# board.net
KiCad netlist of a schematic drawn in EAGLE
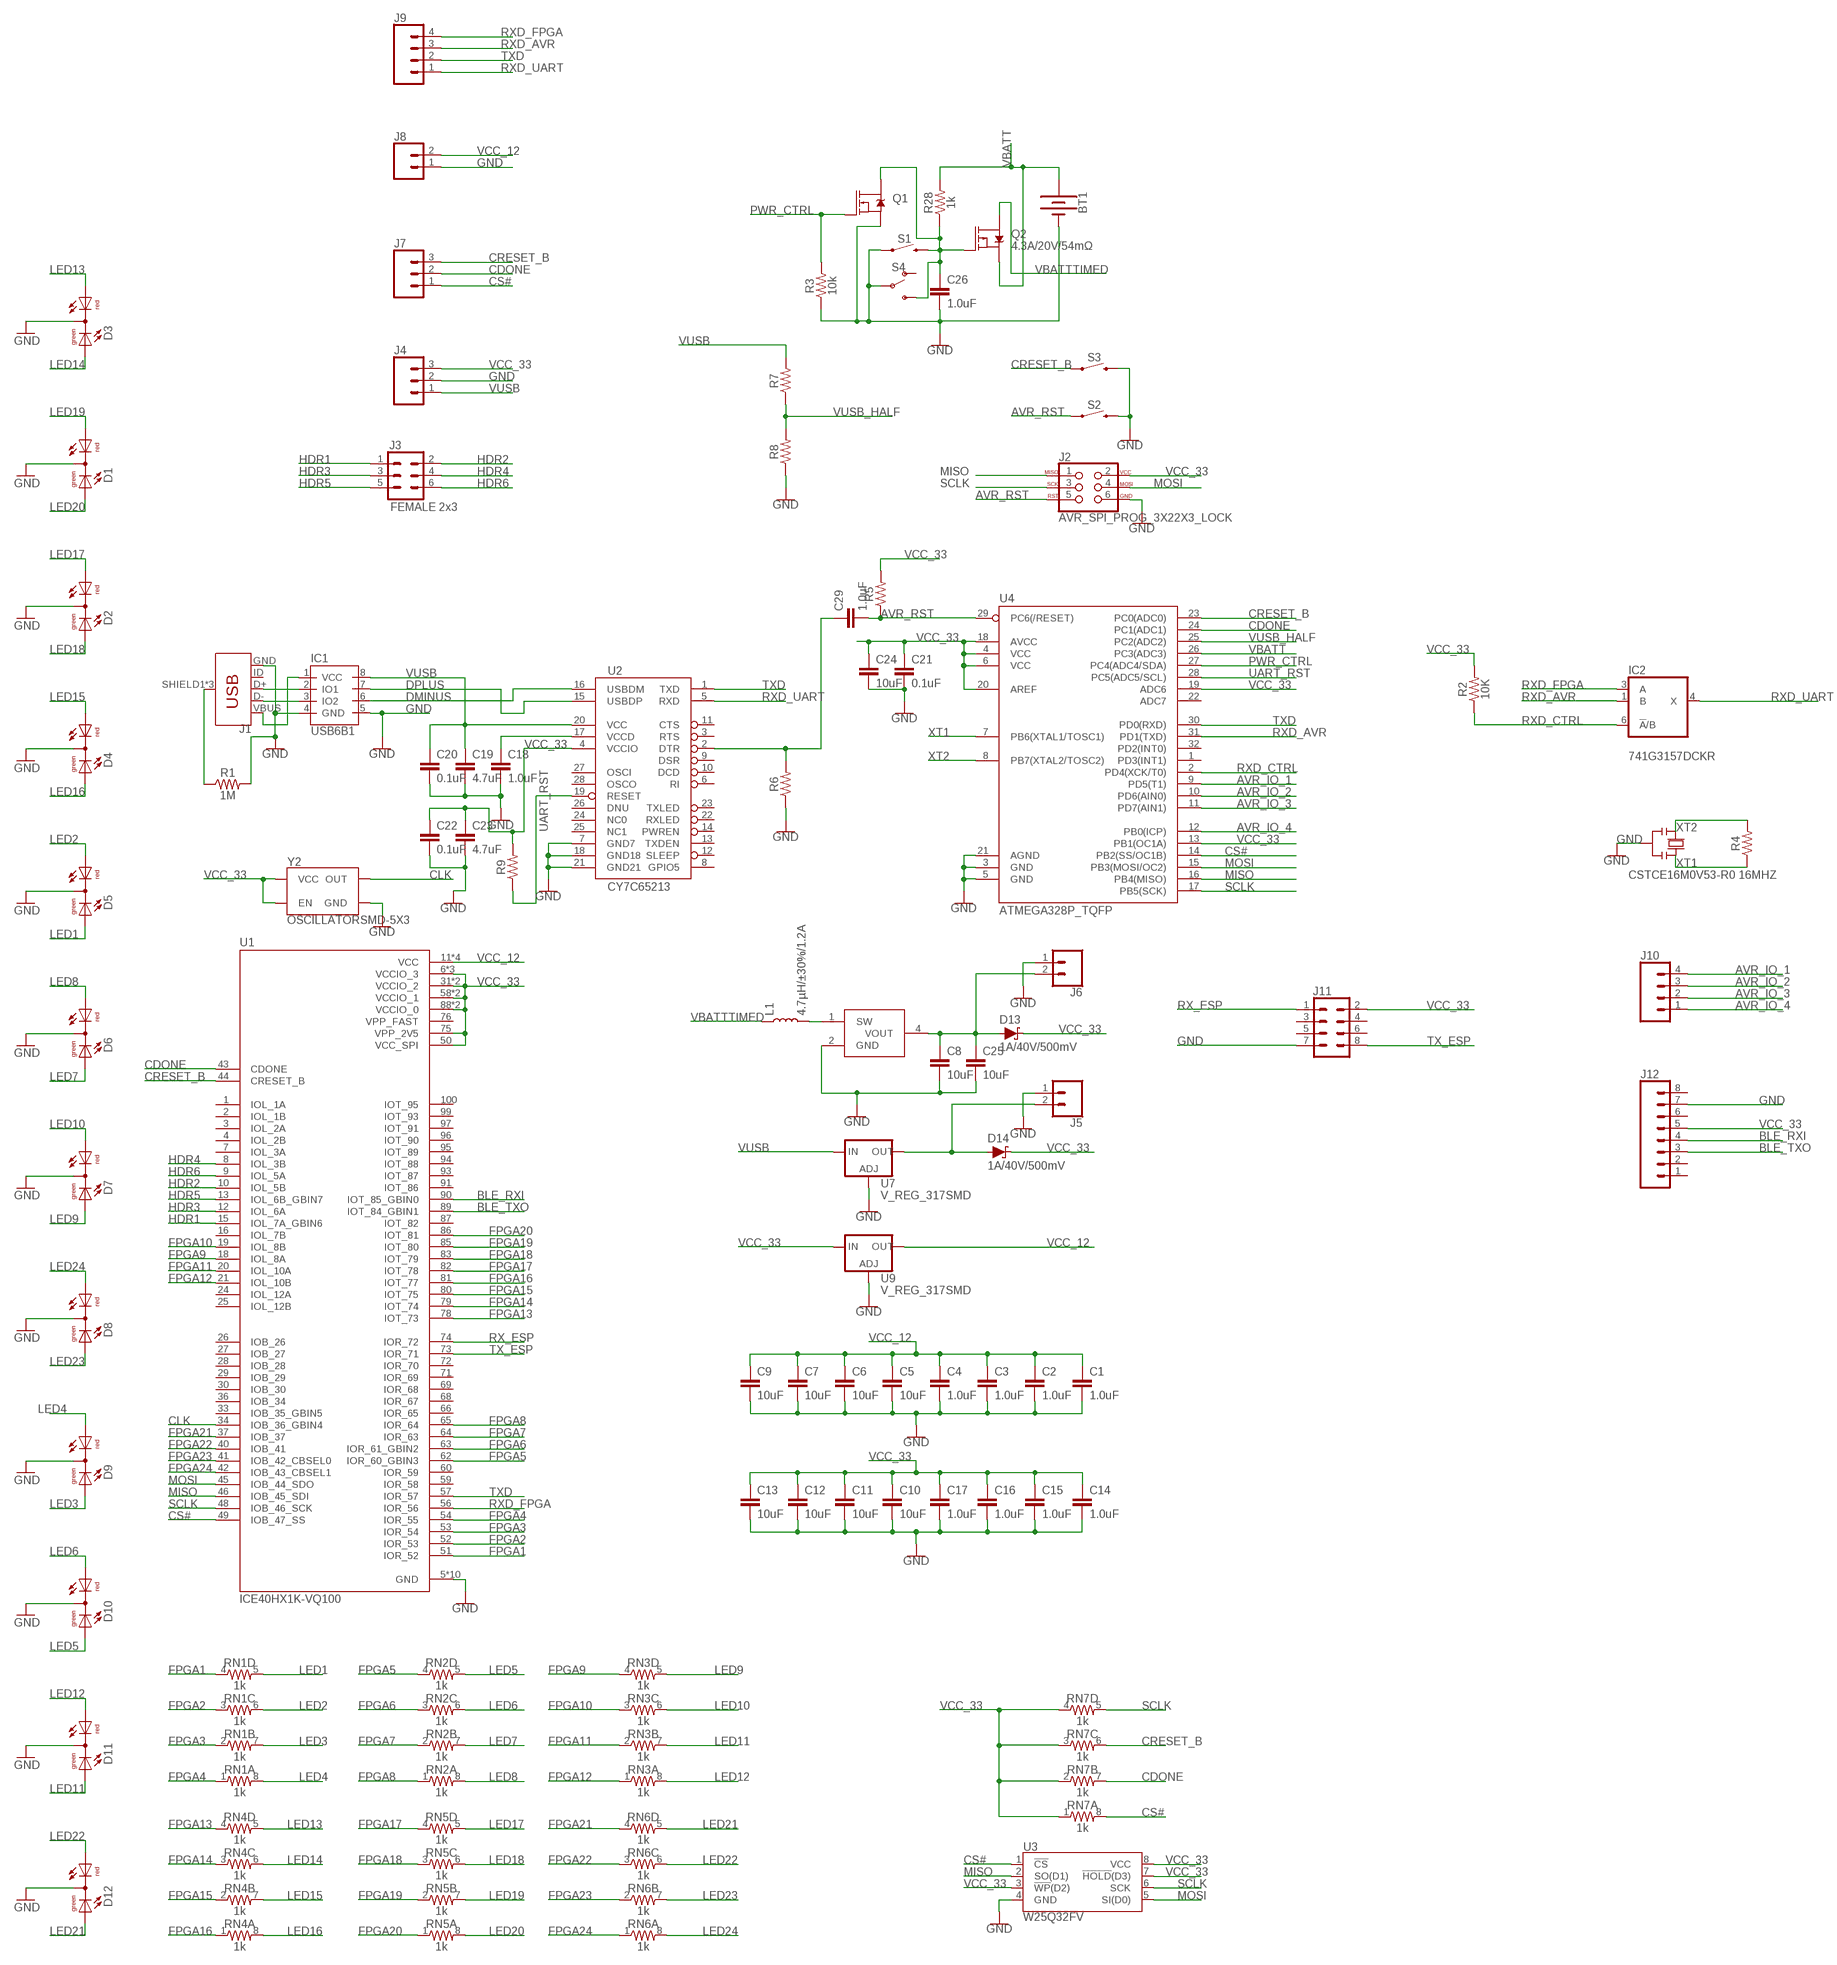
[diagram p0: schematic, sheet 1]

(export (version "E")
  (design (tool "Eeschema 10.0.6"))
  (components
    (comp (ref "BT1")
      (value "BATTERY-20MM_SMD")
      (footprint "eagle-import:BATTCON_20MM")
      (libsource (lib "eagle-import") (part "BATTERY-20MM_SMD"))
    )
    (comp (ref "C1")
      (value "1.0uF")
      (footprint "eagle-import:0805")
      (libsource (lib "eagle-import") (part "1.0UF-0805-25V-10%"))
    )
    (comp (ref "C2")
      (value "1.0uF")
      (footprint "eagle-import:0805")
      (libsource (lib "eagle-import") (part "1.0UF-0805-25V-10%"))
    )
    (comp (ref "C3")
      (value "1.0uF")
      (footprint "eagle-import:0805")
      (libsource (lib "eagle-import") (part "1.0UF-0805-25V-10%"))
    )
    (comp (ref "C4")
      (value "1.0uF")
      (footprint "eagle-import:0805")
      (libsource (lib "eagle-import") (part "1.0UF-0805-25V-10%"))
    )
    (comp (ref "C5")
      (value "10uF")
      (footprint "eagle-import:0805")
      (libsource (lib "eagle-import") (part "10UF-0805-10V-10%"))
    )
    (comp (ref "C6")
      (value "10uF")
      (footprint "eagle-import:0805")
      (libsource (lib "eagle-import") (part "10UF-0805-10V-10%"))
    )
    (comp (ref "C7")
      (value "10uF")
      (footprint "eagle-import:0805")
      (libsource (lib "eagle-import") (part "10UF-0805-10V-10%"))
    )
    (comp (ref "C8")
      (value "10uF")
      (footprint "eagle-import:0805")
      (libsource (lib "eagle-import") (part "22UF-0805-6.3V-20%"))
    )
    (comp (ref "C9")
      (value "10uF")
      (footprint "eagle-import:0805")
      (libsource (lib "eagle-import") (part "10UF-0805-10V-10%"))
    )
    (comp (ref "C10")
      (value "10uF")
      (footprint "eagle-import:0805")
      (libsource (lib "eagle-import") (part "10UF-0805-10V-10%"))
    )
    (comp (ref "C11")
      (value "10uF")
      (footprint "eagle-import:0805")
      (libsource (lib "eagle-import") (part "10UF-0805-10V-10%"))
    )
    (comp (ref "C12")
      (value "10uF")
      (footprint "eagle-import:0805")
      (libsource (lib "eagle-import") (part "10UF-0805-10V-10%"))
    )
    (comp (ref "C13")
      (value "10uF")
      (footprint "eagle-import:0805")
      (libsource (lib "eagle-import") (part "10UF-0805-10V-10%"))
    )
    (comp (ref "C14")
      (value "1.0uF")
      (footprint "eagle-import:0805")
      (libsource (lib "eagle-import") (part "1.0UF-0805-25V-(+80/-20%)"))
    )
    (comp (ref "C15")
      (value "1.0uF")
      (footprint "eagle-import:0805")
      (libsource (lib "eagle-import") (part "1.0UF-0805-25V-(+80/-20%)"))
    )
    (comp (ref "C16")
      (value "1.0uF")
      (footprint "eagle-import:0805")
      (libsource (lib "eagle-import") (part "1.0UF-0805-25V-(+80/-20%)"))
    )
    (comp (ref "C17")
      (value "1.0uF")
      (footprint "eagle-import:0805")
      (libsource (lib "eagle-import") (part "1.0UF-0805-25V-(+80/-20%)"))
    )
    (comp (ref "C18")
      (value "1.0uF")
      (footprint "eagle-import:0805")
      (libsource (lib "eagle-import") (part "1.0UF-0805-25V-10%"))
    )
    (comp (ref "C19")
      (value "4.7uF")
      (footprint "eagle-import:0805")
      (libsource (lib "eagle-import") (part "10UF-0805-10V-10%"))
    )
    (comp (ref "C20")
      (value "0.1uF")
      (footprint "eagle-import:0805")
      (libsource (lib "eagle-import") (part "1.0UF-0805-25V-10%"))
    )
    (comp (ref "C21")
      (value "0.1uF")
      (footprint "eagle-import:0805")
      (libsource (lib "eagle-import") (part "1.0UF-0805-25V-10%"))
    )
    (comp (ref "C22")
      (value "0.1uF")
      (footprint "eagle-import:0805")
      (libsource (lib "eagle-import") (part "1.0UF-0805-25V-10%"))
    )
    (comp (ref "C23")
      (value "4.7uF")
      (footprint "eagle-import:0805")
      (libsource (lib "eagle-import") (part "1.0UF-0805-25V-10%"))
    )
    (comp (ref "C24")
      (value "10uF")
      (footprint "eagle-import:0805")
      (libsource (lib "eagle-import") (part "1.0UF-0805-25V-10%"))
    )
    (comp (ref "C25")
      (value "10uF")
      (footprint "eagle-import:0805")
      (libsource (lib "eagle-import") (part "1.0UF-0805-25V-10%"))
    )
    (comp (ref "C26")
      (value "1.0uF")
      (footprint "eagle-import:0603")
      (libsource (lib "eagle-import") (part "1.0UF-0603-16V-10%"))
    )
    (comp (ref "C29")
      (value "1.0uF")
      (footprint "eagle-import:0805")
      (libsource (lib "eagle-import") (part "1.0UF-0805-25V-(+80/-20%)"))
    )
    (comp (ref "D1")
      (value "DUOLED5MM")
      (footprint "eagle-import:DUOLED5MM")
      (libsource (lib "eagle-import") (part "DUOLED5MM"))
    )
    (comp (ref "D2")
      (value "DUOLED5MM")
      (footprint "eagle-import:DUOLED5MM")
      (libsource (lib "eagle-import") (part "DUOLED5MM"))
    )
    (comp (ref "D3")
      (value "DUOLED5MM")
      (footprint "eagle-import:DUOLED5MM")
      (libsource (lib "eagle-import") (part "DUOLED5MM"))
    )
    (comp (ref "D4")
      (value "DUOLED5MM")
      (footprint "eagle-import:DUOLED5MM")
      (libsource (lib "eagle-import") (part "DUOLED5MM"))
    )
    (comp (ref "D5")
      (value "DUOLED5MM")
      (footprint "eagle-import:DUOLED5MM")
      (libsource (lib "eagle-import") (part "DUOLED5MM"))
    )
    (comp (ref "D6")
      (value "DUOLED5MM")
      (footprint "eagle-import:DUOLED5MM")
      (libsource (lib "eagle-import") (part "DUOLED5MM"))
    )
    (comp (ref "D7")
      (value "DUOLED5MM")
      (footprint "eagle-import:DUOLED5MM")
      (libsource (lib "eagle-import") (part "DUOLED5MM"))
    )
    (comp (ref "D8")
      (value "DUOLED5MM")
      (footprint "eagle-import:DUOLED5MM")
      (libsource (lib "eagle-import") (part "DUOLED5MM"))
    )
    (comp (ref "D9")
      (value "DUOLED5MM")
      (footprint "eagle-import:DUOLED5MM")
      (libsource (lib "eagle-import") (part "DUOLED5MM"))
    )
    (comp (ref "D10")
      (value "DUOLED5MM")
      (footprint "eagle-import:DUOLED5MM")
      (libsource (lib "eagle-import") (part "DUOLED5MM"))
    )
    (comp (ref "D11")
      (value "DUOLED5MM")
      (footprint "eagle-import:DUOLED5MM")
      (libsource (lib "eagle-import") (part "DUOLED5MM"))
    )
    (comp (ref "D12")
      (value "DUOLED5MM")
      (footprint "eagle-import:DUOLED5MM")
      (libsource (lib "eagle-import") (part "DUOLED5MM"))
    )
    (comp (ref "D13")
      (value "1A/40V/500mV")
      (footprint "eagle-import:SMA-DIODE")
      (libsource (lib "eagle-import") (part "DIODE-SCHOTTKY-SS14"))
    )
    (comp (ref "D14")
      (value "1A/40V/500mV")
      (footprint "eagle-import:SMA-DIODE")
      (libsource (lib "eagle-import") (part "DIODE-SCHOTTKY-SS14"))
    )
    (comp (ref "IC1")
      (value "USB6B1")
      (footprint "eagle-import:SO08")
      (libsource (lib "eagle-import") (part "USB6B1"))
    )
    (comp (ref "IC2")
      (value "741G3157DCKR")
      (footprint "eagle-import:DCK_R-PDSO-G6")
      (libsource (lib "eagle-import") (part "741G3157DCKR"))
    )
    (comp (ref "J1")
      (value "USB_MICRO-B_FEMALE-SMT")
      (footprint "eagle-import:USB-B-MICRO-SMD")
      (libsource (lib "eagle-import") (part "USB_MICRO-B_FEMALE-SMT"))
    )
    (comp (ref "J2")
      (value "AVR_SPI_PROG_3X22X3_LOCK")
      (footprint "eagle-import:2X3_LOCK")
      (libsource (lib "eagle-import") (part "AVR_SPI_PROG_3X22X3_LOCK"))
    )
    (comp (ref "J3")
      (value "FEMALE 2x3")
      (footprint "eagle-import:2X3")
      (libsource (lib "eagle-import") (part "CONN_03X2FEMALE"))
    )
    (comp (ref "J4")
      (value "CONN_03LOCK")
      (footprint "eagle-import:1X03_LOCK")
      (libsource (lib "eagle-import") (part "CONN_03LOCK"))
    )
    (comp (ref "J5")
      (value "CONN_02LOCK")
      (footprint "eagle-import:1X02_LOCK")
      (libsource (lib "eagle-import") (part "CONN_02LOCK"))
    )
    (comp (ref "J6")
      (value "CONN_02LOCK")
      (footprint "eagle-import:1X02_LOCK")
      (libsource (lib "eagle-import") (part "CONN_02LOCK"))
    )
    (comp (ref "J7")
      (value "CONN_03LOCK")
      (footprint "eagle-import:1X03_LOCK")
      (libsource (lib "eagle-import") (part "CONN_03LOCK"))
    )
    (comp (ref "J8")
      (value "CONN_02LOCK")
      (footprint "eagle-import:1X02_LOCK")
      (libsource (lib "eagle-import") (part "CONN_02LOCK"))
    )
    (comp (ref "J9")
      (value "CONN_04LOCK")
      (footprint "eagle-import:1X04_LOCK")
      (libsource (lib "eagle-import") (part "CONN_04LOCK"))
    )
    (comp (ref "J10")
      (value "CONN_04LOCK")
      (footprint "eagle-import:1X04_LOCK")
      (libsource (lib "eagle-import") (part "CONN_04LOCK"))
    )
    (comp (ref "J11")
      (value "CONN_04X2")
      (footprint "eagle-import:2X4")
      (libsource (lib "eagle-import") (part "CONN_04X2"))
    )
    (comp (ref "J12")
      (value "CONN_08LOCK")
      (footprint "eagle-import:1X08_LOCK")
      (libsource (lib "eagle-import") (part "CONN_08LOCK"))
    )
    (comp (ref "L1")
      (value "4.7µH/±30%/1.2A")
      (footprint "eagle-import:INDUCTOR_4.7UH")
      (libsource (lib "eagle-import") (part "INDUCTOR-CDRH-4.7UH"))
    )
    (comp (ref "Q1")
      (value "5.8A/30V/35mΩ")
      (footprint "eagle-import:SOT23-3")
      (libsource (lib "eagle-import") (part "MOSFET-NCH-AO3404A"))
    )
    (comp (ref "Q2")
      (value "4.3A/20V/54mΩ")
      (footprint "eagle-import:SOT23-3")
      (libsource (lib "eagle-import") (part "MOSFET_PCH-IRLML2244"))
    )
    (comp (ref "R1")
      (value "1M")
      (footprint "eagle-import:0805")
      (libsource (lib "eagle-import") (part "RESISTOR0805"))
    )
    (comp (ref "R2")
      (value "10K")
      (footprint "eagle-import:0805")
      (libsource (lib "eagle-import") (part "RESISTOR0805"))
    )
    (comp (ref "R3")
      (value "10k")
      (footprint "eagle-import:0805")
      (libsource (lib "eagle-import") (part "RESISTOR0805"))
    )
    (comp (ref "R4")
      (value "RESISTOR0805")
      (footprint "eagle-import:0805")
      (libsource (lib "eagle-import") (part "RESISTOR0805"))
    )
    (comp (ref "R5")
      (value "RESISTOR0805")
      (footprint "eagle-import:0805")
      (libsource (lib "eagle-import") (part "RESISTOR0805"))
    )
    (comp (ref "R6")
      (value "RESISTOR0805")
      (footprint "eagle-import:0805")
      (libsource (lib "eagle-import") (part "RESISTOR0805"))
    )
    (comp (ref "R7")
      (value "RESISTOR0805")
      (footprint "eagle-import:0805")
      (libsource (lib "eagle-import") (part "RESISTOR0805"))
    )
    (comp (ref "R8")
      (value "RESISTOR0805")
      (footprint "eagle-import:0805")
      (libsource (lib "eagle-import") (part "RESISTOR0805"))
    )
    (comp (ref "R9")
      (value "RESISTOR0805")
      (footprint "eagle-import:0805")
      (libsource (lib "eagle-import") (part "RESISTOR0805"))
    )
    (comp (ref "R28")
      (value "1k")
      (footprint "eagle-import:0603")
      (libsource (lib "eagle-import") (part "1KOHM-0603-1/10W-1%"))
    )
    (comp (ref "RN1")
      (value "1k")
      (footprint "eagle-import:0805-ARV")
      (libsource (lib "eagle-import") (part "1KOHM-ARRAY(4)-0805_ARV-1/10W-5%"))
    )
    (comp (ref "RN2")
      (value "1k")
      (footprint "eagle-import:0805-ARV")
      (libsource (lib "eagle-import") (part "1KOHM-ARRAY(4)-0805_ARV-1/10W-5%"))
    )
    (comp (ref "RN3")
      (value "1k")
      (footprint "eagle-import:0805-ARV")
      (libsource (lib "eagle-import") (part "1KOHM-ARRAY(4)-0805_ARV-1/10W-5%"))
    )
    (comp (ref "RN4")
      (value "1k")
      (footprint "eagle-import:0805-ARV")
      (libsource (lib "eagle-import") (part "1KOHM-ARRAY(4)-0805_ARV-1/10W-5%"))
    )
    (comp (ref "RN5")
      (value "1k")
      (footprint "eagle-import:0805-ARV")
      (libsource (lib "eagle-import") (part "1KOHM-ARRAY(4)-0805_ARV-1/10W-5%"))
    )
    (comp (ref "RN6")
      (value "1k")
      (footprint "eagle-import:0805-ARV")
      (libsource (lib "eagle-import") (part "1KOHM-ARRAY(4)-0805_ARV-1/10W-5%"))
    )
    (comp (ref "RN7")
      (value "1k")
      (footprint "eagle-import:0805-ARV")
      (libsource (lib "eagle-import") (part "1KOHM-ARRAY(4)-0805_ARV-1/10W-5%"))
    )
    (comp (ref "S1")
      (value "MOMENTARY-SWITCH-SPST-SMD-5.2MM")
      (footprint "eagle-import:TACTILE_SWITCH_SMD_5.2MM")
      (libsource (lib "eagle-import") (part "MOMENTARY-SWITCH-SPST-SMD-5.2MM"))
    )
    (comp (ref "S2")
      (value "MOMENTARY-SWITCH-SPST-SMD-5.2MM")
      (footprint "eagle-import:TACTILE_SWITCH_SMD_5.2MM")
      (libsource (lib "eagle-import") (part "MOMENTARY-SWITCH-SPST-SMD-5.2MM"))
    )
    (comp (ref "S3")
      (value "MOMENTARY-SWITCH-SPST-SMD-5.2MM")
      (footprint "eagle-import:TACTILE_SWITCH_SMD_5.2MM")
      (libsource (lib "eagle-import") (part "MOMENTARY-SWITCH-SPST-SMD-5.2MM"))
    )
    (comp (ref "S4")
      (value "SWITCH-SPDT-PTH-11.6X4.0MM")
      (footprint "eagle-import:SWITCH_SPDT_PTH_11.6X4.0MM")
      (libsource (lib "eagle-import") (part "SWITCH-SPDT-PTH-11.6X4.0MM"))
    )
    (comp (ref "U$2")
      (value "TPS613221A")
      (footprint "eagle-import:SOT95P280X145-5N")
      (libsource (lib "eagle-import") (part "TPS613221A"))
    )
    (comp (ref "U1")
      (value "ICE40HX1K-VQ100")
      (footprint "eagle-import:QFP50P1600X1600X120-100N")
      (fields (field (name "MF") "Lattice Semiconductor"))
      (libsource (lib "eagle-import") (part "ICE40HX1K-VQ100"))
    )
    (comp (ref "U2")
      (value "CY7C65213")
      (footprint "eagle-import:SSOP28DB")
      (libsource (lib "eagle-import") (part "CY7C65213"))
    )
    (comp (ref "U3")
      (value "W25Q32FV")
      (footprint "eagle-import:SOIC-8")
      (libsource (lib "eagle-import") (part "W25Q32FVSS"))
    )
    (comp (ref "U4")
      (value "ATMEGA328P_TQFP")
      (footprint "eagle-import:TQFP32-08")
      (libsource (lib "eagle-import") (part "ATMEGA328P_TQFP"))
    )
    (comp (ref "U7")
      (value "V_REG_317SMD")
      (footprint "eagle-import:SOT223")
      (libsource (lib "eagle-import") (part "V_REG_317SMD"))
    )
    (comp (ref "U9")
      (value "V_REG_317SMD")
      (footprint "eagle-import:SOT223")
      (libsource (lib "eagle-import") (part "V_REG_317SMD"))
    )
    (comp (ref "Y1")
      (value "CSTCE16M0V53-R0 16MHZ")
      (footprint "eagle-import:RESONATOR")
      (libsource (lib "eagle-import") (part "RESONATORMU"))
    )
    (comp (ref "Y2")
      (value "OSCILLATORSMD-5X3")
      (footprint "eagle-import:OSCILLATOR-SMD-5X3.2")
      (libsource (lib "eagle-import") (part "OSCILLATORSMD-5X3"))
    )
  )
  (nets
    (net (code "1") (name "/AVR_IO_1") (class "Default")
      (node (ref "J10") (pin "4") (pinfunction "4_4") (pintype "passive"))
      (node (ref "U4") (pin "9") (pinfunction "PD5(T1)_9") (pintype "bidirectional"))
    )
    (net (code "2") (name "/AVR_IO_2") (class "Default")
      (node (ref "J10") (pin "3") (pinfunction "3_3") (pintype "passive"))
      (node (ref "U4") (pin "10") (pinfunction "PD6(AIN0)_10") (pintype "bidirectional"))
    )
    (net (code "3") (name "/AVR_IO_3") (class "Default")
      (node (ref "J10") (pin "2") (pinfunction "2_2") (pintype "passive"))
      (node (ref "U4") (pin "11") (pinfunction "PD7(AIN1)_11") (pintype "bidirectional"))
    )
    (net (code "4") (name "/AVR_IO_4") (class "Default")
      (node (ref "J10") (pin "1") (pinfunction "1_1") (pintype "passive"))
      (node (ref "U4") (pin "12") (pinfunction "PB0(ICP)_12") (pintype "bidirectional"))
    )
    (net (code "5") (name "/AVR_RST") (class "Default")
      (node (ref "C29") (pin "2") (pinfunction "2_2") (pintype "passive"))
      (node (ref "J2") (pin "5") (pinfunction "5_5") (pintype "passive"))
      (node (ref "R5") (pin "1") (pinfunction "1_1") (pintype "passive"))
      (node (ref "S2") (pin "1") (pinfunction "1_1") (pintype "passive"))
      (node (ref "U4") (pin "29") (pinfunction "PC6(/RESET)_29") (pintype "bidirectional"))
    )
    (net (code "6") (name "/BLE_RXI") (class "Default")
      (node (ref "J12") (pin "4") (pinfunction "4_4") (pintype "passive"))
      (node (ref "U1") (pin "90") (pinfunction "IOT_85_GBIN0_90") (pintype "bidirectional"))
    )
    (net (code "7") (name "/BLE_TXO") (class "Default")
      (node (ref "J12") (pin "3") (pinfunction "3_3") (pintype "passive"))
      (node (ref "U1") (pin "89") (pinfunction "IOT_84_GBIN1_89") (pintype "bidirectional"))
    )
    (net (code "8") (name "/CDONE") (class "Default")
      (node (ref "J7") (pin "2") (pinfunction "2_2") (pintype "passive"))
      (node (ref "RN7") (pin "7") (pinfunction "2_7") (pintype "passive"))
      (node (ref "U1") (pin "43") (pinfunction "CDONE_43") (pintype "input"))
      (node (ref "U4") (pin "24") (pinfunction "PC1(ADC1)_24") (pintype "bidirectional"))
    )
    (net (code "9") (name "/CLK") (class "Default")
      (node (ref "U1") (pin "34") (pinfunction "IOB_36_GBIN4_34") (pintype "bidirectional"))
      (node (ref "Y2") (pin "3") (pinfunction "OUT_3") (pintype "bidirectional"))
    )
    (net (code "10") (name "/CRESET_B") (class "Default")
      (node (ref "J7") (pin "3") (pinfunction "3_3") (pintype "passive"))
      (node (ref "RN7") (pin "6") (pinfunction "2_6") (pintype "passive"))
      (node (ref "S3") (pin "1") (pinfunction "1_1") (pintype "passive"))
      (node (ref "U1") (pin "44") (pinfunction "CRESET_B_44") (pintype "input"))
      (node (ref "U4") (pin "23") (pinfunction "PC0(ADC0)_23") (pintype "bidirectional"))
    )
    (net (code "11") (name "/CS#") (class "Default")
      (node (ref "J7") (pin "1") (pinfunction "1_1") (pintype "passive"))
      (node (ref "RN7") (pin "8") (pinfunction "2_8") (pintype "passive"))
      (node (ref "U1") (pin "49") (pinfunction "IOB_47_SS_49") (pintype "bidirectional"))
      (node (ref "U3") (pin "1") (pinfunction "~{CS}_1") (pintype "bidirectional"))
      (node (ref "U4") (pin "14") (pinfunction "PB2(SS/OC1B)_14") (pintype "bidirectional"))
    )
    (net (code "12") (name "/DMINUS") (class "Default")
      (node (ref "IC1") (pin "6") (pinfunction "IO2_6") (pintype "bidirectional"))
      (node (ref "U2") (pin "16") (pinfunction "USBDM_16") (pintype "bidirectional"))
    )
    (net (code "13") (name "/DPLUS") (class "Default")
      (node (ref "IC1") (pin "7") (pinfunction "IO1_7") (pintype "bidirectional"))
      (node (ref "U2") (pin "15") (pinfunction "USBDP_15") (pintype "bidirectional"))
    )
    (net (code "14") (name "/FPGA1") (class "Default")
      (node (ref "RN1") (pin "4") (pinfunction "1_4") (pintype "passive"))
      (node (ref "U1") (pin "51") (pinfunction "IOR_52_51") (pintype "bidirectional"))
    )
    (net (code "15") (name "/FPGA2") (class "Default")
      (node (ref "RN1") (pin "3") (pinfunction "1_3") (pintype "passive"))
      (node (ref "U1") (pin "52") (pinfunction "IOR_53_52") (pintype "bidirectional"))
    )
    (net (code "16") (name "/FPGA3") (class "Default")
      (node (ref "RN1") (pin "2") (pinfunction "1_2") (pintype "passive"))
      (node (ref "U1") (pin "53") (pinfunction "IOR_54_53") (pintype "bidirectional"))
    )
    (net (code "17") (name "/FPGA4") (class "Default")
      (node (ref "RN1") (pin "1") (pinfunction "1_1") (pintype "passive"))
      (node (ref "U1") (pin "54") (pinfunction "IOR_55_54") (pintype "bidirectional"))
    )
    (net (code "18") (name "/FPGA5") (class "Default")
      (node (ref "RN2") (pin "4") (pinfunction "1_4") (pintype "passive"))
      (node (ref "U1") (pin "62") (pinfunction "IOR_60_GBIN3_62") (pintype "bidirectional"))
    )
    (net (code "19") (name "/FPGA6") (class "Default")
      (node (ref "RN2") (pin "3") (pinfunction "1_3") (pintype "passive"))
      (node (ref "U1") (pin "63") (pinfunction "IOR_61_GBIN2_63") (pintype "bidirectional"))
    )
    (net (code "20") (name "/FPGA7") (class "Default")
      (node (ref "RN2") (pin "2") (pinfunction "1_2") (pintype "passive"))
      (node (ref "U1") (pin "64") (pinfunction "IOR_63_64") (pintype "bidirectional"))
    )
    (net (code "21") (name "/FPGA8") (class "Default")
      (node (ref "RN2") (pin "1") (pinfunction "1_1") (pintype "passive"))
      (node (ref "U1") (pin "65") (pinfunction "IOR_64_65") (pintype "bidirectional"))
    )
    (net (code "22") (name "/FPGA9") (class "Default")
      (node (ref "RN3") (pin "4") (pinfunction "1_4") (pintype "passive"))
      (node (ref "U1") (pin "18") (pinfunction "IOL_8A_18") (pintype "bidirectional"))
    )
    (net (code "23") (name "/FPGA10") (class "Default")
      (node (ref "RN3") (pin "3") (pinfunction "1_3") (pintype "passive"))
      (node (ref "U1") (pin "19") (pinfunction "IOL_8B_19") (pintype "bidirectional"))
    )
    (net (code "24") (name "/FPGA11") (class "Default")
      (node (ref "RN3") (pin "2") (pinfunction "1_2") (pintype "passive"))
      (node (ref "U1") (pin "20") (pinfunction "IOL_10A_20") (pintype "bidirectional"))
    )
    (net (code "25") (name "/FPGA12") (class "Default")
      (node (ref "RN3") (pin "1") (pinfunction "1_1") (pintype "passive"))
      (node (ref "U1") (pin "21") (pinfunction "IOL_10B_21") (pintype "bidirectional"))
    )
    (net (code "26") (name "/FPGA13") (class "Default")
      (node (ref "RN4") (pin "4") (pinfunction "1_4") (pintype "passive"))
      (node (ref "U1") (pin "78") (pinfunction "IOT_73_78") (pintype "bidirectional"))
    )
    (net (code "27") (name "/FPGA14") (class "Default")
      (node (ref "RN4") (pin "3") (pinfunction "1_3") (pintype "passive"))
      (node (ref "U1") (pin "79") (pinfunction "IOT_74_79") (pintype "bidirectional"))
    )
    (net (code "28") (name "/FPGA15") (class "Default")
      (node (ref "RN4") (pin "2") (pinfunction "1_2") (pintype "passive"))
      (node (ref "U1") (pin "80") (pinfunction "IOT_75_80") (pintype "bidirectional"))
    )
    (net (code "29") (name "/FPGA16") (class "Default")
      (node (ref "RN4") (pin "1") (pinfunction "1_1") (pintype "passive"))
      (node (ref "U1") (pin "81") (pinfunction "IOT_77_81") (pintype "bidirectional"))
    )
    (net (code "30") (name "/FPGA17") (class "Default")
      (node (ref "RN5") (pin "4") (pinfunction "1_4") (pintype "passive"))
      (node (ref "U1") (pin "82") (pinfunction "IOT_78_82") (pintype "bidirectional"))
    )
    (net (code "31") (name "/FPGA18") (class "Default")
      (node (ref "RN5") (pin "3") (pinfunction "1_3") (pintype "passive"))
      (node (ref "U1") (pin "83") (pinfunction "IOT_79_83") (pintype "bidirectional"))
    )
    (net (code "32") (name "/FPGA19") (class "Default")
      (node (ref "RN5") (pin "2") (pinfunction "1_2") (pintype "passive"))
      (node (ref "U1") (pin "85") (pinfunction "IOT_80_85") (pintype "bidirectional"))
    )
    (net (code "33") (name "/FPGA20") (class "Default")
      (node (ref "RN5") (pin "1") (pinfunction "1_1") (pintype "passive"))
      (node (ref "U1") (pin "86") (pinfunction "IOT_81_86") (pintype "bidirectional"))
    )
    (net (code "34") (name "/FPGA21") (class "Default")
      (node (ref "RN6") (pin "4") (pinfunction "1_4") (pintype "passive"))
      (node (ref "U1") (pin "37") (pinfunction "IOB_37_37") (pintype "bidirectional"))
    )
    (net (code "35") (name "/FPGA22") (class "Default")
      (node (ref "RN6") (pin "3") (pinfunction "1_3") (pintype "passive"))
      (node (ref "U1") (pin "40") (pinfunction "IOB_41_40") (pintype "bidirectional"))
    )
    (net (code "36") (name "/FPGA23") (class "Default")
      (node (ref "RN6") (pin "2") (pinfunction "1_2") (pintype "passive"))
      (node (ref "U1") (pin "41") (pinfunction "IOB_42_CBSEL0_41") (pintype "bidirectional"))
    )
    (net (code "37") (name "/FPGA24") (class "Default")
      (node (ref "RN6") (pin "1") (pinfunction "1_1") (pintype "passive"))
      (node (ref "U1") (pin "42") (pinfunction "IOB_43_CBSEL1_42") (pintype "bidirectional"))
    )
    (net (code "38") (name "/HDR1") (class "Default")
      (node (ref "J3") (pin "1") (pinfunction "1_1") (pintype "bidirectional"))
      (node (ref "U1") (pin "15") (pinfunction "IOL_7A_GBIN6_15") (pintype "bidirectional"))
    )
    (net (code "39") (name "/HDR2") (class "Default")
      (node (ref "J3") (pin "2") (pinfunction "2_2") (pintype "bidirectional"))
      (node (ref "U1") (pin "10") (pinfunction "IOL_5B_10") (pintype "bidirectional"))
    )
    (net (code "40") (name "/HDR3") (class "Default")
      (node (ref "J3") (pin "3") (pinfunction "3_3") (pintype "bidirectional"))
      (node (ref "U1") (pin "12") (pinfunction "IOL_6A_12") (pintype "bidirectional"))
    )
    (net (code "41") (name "/HDR4") (class "Default")
      (node (ref "J3") (pin "4") (pinfunction "4_4") (pintype "bidirectional"))
      (node (ref "U1") (pin "8") (pinfunction "IOL_3B_8") (pintype "bidirectional"))
    )
    (net (code "42") (name "/HDR5") (class "Default")
      (node (ref "J3") (pin "5") (pinfunction "5_5") (pintype "bidirectional"))
      (node (ref "U1") (pin "13") (pinfunction "IOL_6B_GBIN7_13") (pintype "bidirectional"))
    )
    (net (code "43") (name "/HDR6") (class "Default")
      (node (ref "J3") (pin "6") (pinfunction "6_6") (pintype "bidirectional"))
      (node (ref "U1") (pin "9") (pinfunction "IOL_5A_9") (pintype "bidirectional"))
    )
    (net (code "44") (name "/LED1") (class "Default")
      (node (ref "D5") (pin "AG") (pinfunction "AG_AG") (pintype "passive"))
      (node (ref "RN1") (pin "5") (pinfunction "2_5") (pintype "passive"))
    )
    (net (code "45") (name "/LED2") (class "Default")
      (node (ref "D5") (pin "AR") (pinfunction "AR_AR") (pintype "passive"))
      (node (ref "RN1") (pin "6") (pinfunction "2_6") (pintype "passive"))
    )
    (net (code "46") (name "/LED3") (class "Default")
      (node (ref "D9") (pin "AG") (pinfunction "AG_AG") (pintype "passive"))
      (node (ref "RN1") (pin "7") (pinfunction "2_7") (pintype "passive"))
    )
    (net (code "47") (name "/LED4") (class "Default")
      (node (ref "D9") (pin "AR") (pinfunction "AR_AR") (pintype "passive"))
      (node (ref "RN1") (pin "8") (pinfunction "2_8") (pintype "passive"))
    )
    (net (code "48") (name "/LED5") (class "Default")
      (node (ref "D10") (pin "AG") (pinfunction "AG_AG") (pintype "passive"))
      (node (ref "RN2") (pin "5") (pinfunction "2_5") (pintype "passive"))
    )
    (net (code "49") (name "/LED6") (class "Default")
      (node (ref "D10") (pin "AR") (pinfunction "AR_AR") (pintype "passive"))
      (node (ref "RN2") (pin "6") (pinfunction "2_6") (pintype "passive"))
    )
    (net (code "50") (name "/LED7") (class "Default")
      (node (ref "D6") (pin "AG") (pinfunction "AG_AG") (pintype "passive"))
      (node (ref "RN2") (pin "7") (pinfunction "2_7") (pintype "passive"))
    )
    (net (code "51") (name "/LED8") (class "Default")
      (node (ref "D6") (pin "AR") (pinfunction "AR_AR") (pintype "passive"))
      (node (ref "RN2") (pin "8") (pinfunction "2_8") (pintype "passive"))
    )
    (net (code "52") (name "/LED9") (class "Default")
      (node (ref "D7") (pin "AG") (pinfunction "AG_AG") (pintype "passive"))
      (node (ref "RN3") (pin "5") (pinfunction "2_5") (pintype "passive"))
    )
    (net (code "53") (name "/LED10") (class "Default")
      (node (ref "D7") (pin "AR") (pinfunction "AR_AR") (pintype "passive"))
      (node (ref "RN3") (pin "6") (pinfunction "2_6") (pintype "passive"))
    )
    (net (code "54") (name "/LED11") (class "Default")
      (node (ref "D11") (pin "AG") (pinfunction "AG_AG") (pintype "passive"))
      (node (ref "RN3") (pin "7") (pinfunction "2_7") (pintype "passive"))
    )
    (net (code "55") (name "/LED12") (class "Default")
      (node (ref "D11") (pin "AR") (pinfunction "AR_AR") (pintype "passive"))
      (node (ref "RN3") (pin "8") (pinfunction "2_8") (pintype "passive"))
    )
    (net (code "56") (name "/LED13") (class "Default")
      (node (ref "D3") (pin "AR") (pinfunction "AR_AR") (pintype "passive"))
      (node (ref "RN4") (pin "5") (pinfunction "2_5") (pintype "passive"))
    )
    (net (code "57") (name "/LED14") (class "Default")
      (node (ref "D3") (pin "AG") (pinfunction "AG_AG") (pintype "passive"))
      (node (ref "RN4") (pin "6") (pinfunction "2_6") (pintype "passive"))
    )
    (net (code "58") (name "/LED15") (class "Default")
      (node (ref "D4") (pin "AR") (pinfunction "AR_AR") (pintype "passive"))
      (node (ref "RN4") (pin "7") (pinfunction "2_7") (pintype "passive"))
    )
    (net (code "59") (name "/LED16") (class "Default")
      (node (ref "D4") (pin "AG") (pinfunction "AG_AG") (pintype "passive"))
      (node (ref "RN4") (pin "8") (pinfunction "2_8") (pintype "passive"))
    )
    (net (code "60") (name "/LED17") (class "Default")
      (node (ref "D2") (pin "AR") (pinfunction "AR_AR") (pintype "passive"))
      (node (ref "RN5") (pin "5") (pinfunction "2_5") (pintype "passive"))
    )
    (net (code "61") (name "/LED18") (class "Default")
      (node (ref "D2") (pin "AG") (pinfunction "AG_AG") (pintype "passive"))
      (node (ref "RN5") (pin "6") (pinfunction "2_6") (pintype "passive"))
    )
    (net (code "62") (name "/LED19") (class "Default")
      (node (ref "D1") (pin "AR") (pinfunction "AR_AR") (pintype "passive"))
      (node (ref "RN5") (pin "7") (pinfunction "2_7") (pintype "passive"))
    )
    (net (code "63") (name "/LED20") (class "Default")
      (node (ref "D1") (pin "AG") (pinfunction "AG_AG") (pintype "passive"))
      (node (ref "RN5") (pin "8") (pinfunction "2_8") (pintype "passive"))
    )
    (net (code "64") (name "/LED21") (class "Default")
      (node (ref "D12") (pin "AG") (pinfunction "AG_AG") (pintype "passive"))
      (node (ref "RN6") (pin "5") (pinfunction "2_5") (pintype "passive"))
    )
    (net (code "65") (name "/LED22") (class "Default")
      (node (ref "D12") (pin "AR") (pinfunction "AR_AR") (pintype "passive"))
      (node (ref "RN6") (pin "6") (pinfunction "2_6") (pintype "passive"))
    )
    (net (code "66") (name "/LED23") (class "Default")
      (node (ref "D8") (pin "AG") (pinfunction "AG_AG") (pintype "passive"))
      (node (ref "RN6") (pin "7") (pinfunction "2_7") (pintype "passive"))
    )
    (net (code "67") (name "/LED24") (class "Default")
      (node (ref "D8") (pin "AR") (pinfunction "AR_AR") (pintype "passive"))
      (node (ref "RN6") (pin "8") (pinfunction "2_8") (pintype "passive"))
    )
    (net (code "68") (name "/MISO") (class "Default")
      (node (ref "J2") (pin "1") (pinfunction "1_1") (pintype "passive"))
      (node (ref "U1") (pin "46") (pinfunction "IOB_45_SDI_46") (pintype "bidirectional"))
      (node (ref "U3") (pin "2") (pinfunction "SO(D1)_2") (pintype "bidirectional"))
      (node (ref "U4") (pin "16") (pinfunction "PB4(MISO)_16") (pintype "bidirectional"))
    )
    (net (code "69") (name "/MOSI") (class "Default")
      (node (ref "J2") (pin "4") (pinfunction "4_4") (pintype "passive"))
      (node (ref "U1") (pin "45") (pinfunction "IOB_44_SDO_45") (pintype "bidirectional"))
      (node (ref "U3") (pin "5") (pinfunction "SI(D0)_5") (pintype "bidirectional"))
      (node (ref "U4") (pin "15") (pinfunction "PB3(MOSI/OC2)_15") (pintype "bidirectional"))
    )
    (net (code "70") (name "/NC1") (class "Default")
      (node (ref "U2") (pin "25") (pinfunction "NC1_25") (pintype "power_in"))
    )
    (net (code "71") (name "/PWR_CTRL") (class "Default")
      (node (ref "Q1") (pin "1") (pinfunction "G_1") (pintype "bidirectional"))
      (node (ref "R3") (pin "2") (pinfunction "2_2") (pintype "passive"))
      (node (ref "U4") (pin "27") (pinfunction "PC4(ADC4/SDA)_27") (pintype "bidirectional"))
    )
    (net (code "72") (name "/RXD_AVR") (class "Default")
      (node (ref "IC2") (pin "1") (pinfunction "B_1") (pintype "bidirectional"))
      (node (ref "J9") (pin "3") (pinfunction "3_3") (pintype "passive"))
      (node (ref "U4") (pin "31") (pinfunction "PD1(TXD)_31") (pintype "bidirectional"))
    )
    (net (code "73") (name "/RXD_CTRL") (class "Default")
      (node (ref "IC2") (pin "6") (pinfunction "~{A}/B_6") (pintype "input"))
      (node (ref "R2") (pin "1") (pinfunction "1_1") (pintype "passive"))
      (node (ref "U4") (pin "2") (pinfunction "PD4(XCK/T0)_2") (pintype "bidirectional"))
    )
    (net (code "74") (name "/RXD_FPGA") (class "Default")
      (node (ref "IC2") (pin "3") (pinfunction "A_3") (pintype "bidirectional"))
      (node (ref "J9") (pin "4") (pinfunction "4_4") (pintype "passive"))
      (node (ref "U1") (pin "56") (pinfunction "IOR_56_56") (pintype "bidirectional"))
    )
    (net (code "75") (name "/RXD_UART") (class "Default")
      (node (ref "IC2") (pin "4") (pinfunction "X_4") (pintype "bidirectional"))
      (node (ref "J9") (pin "1") (pinfunction "1_1") (pintype "passive"))
      (node (ref "U2") (pin "5") (pinfunction "RXD_5") (pintype "input"))
    )
    (net (code "76") (name "/RX_ESP") (class "Default")
      (node (ref "J11") (pin "1") (pinfunction "1_1") (pintype "passive"))
      (node (ref "U1") (pin "74") (pinfunction "IOR_72_74") (pintype "bidirectional"))
    )
    (net (code "77") (name "/SCLK") (class "Default")
      (node (ref "J2") (pin "3") (pinfunction "3_3") (pintype "passive"))
      (node (ref "RN7") (pin "5") (pinfunction "2_5") (pintype "passive"))
      (node (ref "U1") (pin "48") (pinfunction "IOB_46_SCK_48") (pintype "bidirectional"))
      (node (ref "U3") (pin "6") (pinfunction "SCK_6") (pintype "bidirectional"))
      (node (ref "U4") (pin "17") (pinfunction "PB5(SCK)_17") (pintype "bidirectional"))
    )
    (net (code "78") (name "/TXD") (class "Default")
      (node (ref "J9") (pin "2") (pinfunction "2_2") (pintype "passive"))
      (node (ref "U1") (pin "57") (pinfunction "IOR_57_57") (pintype "bidirectional"))
      (node (ref "U2") (pin "1") (pinfunction "TXD_1") (pintype "output"))
      (node (ref "U4") (pin "30") (pinfunction "PD0(RXD)_30") (pintype "bidirectional"))
    )
    (net (code "79") (name "/TX_ESP") (class "Default")
      (node (ref "J11") (pin "8") (pinfunction "8_8") (pintype "passive"))
      (node (ref "U1") (pin "73") (pinfunction "IOR_71_73") (pintype "bidirectional"))
    )
    (net (code "80") (name "/UART_RST") (class "Default")
      (node (ref "R9") (pin "1") (pinfunction "1_1") (pintype "passive"))
      (node (ref "U2") (pin "19") (pinfunction "RESET_19") (pintype "input"))
      (node (ref "U4") (pin "28") (pinfunction "PC5(ADC5/SCL)_28") (pintype "bidirectional"))
    )
    (net (code "81") (name "/VBATT") (class "Default")
      (node (ref "BT1") (pin "1") (pinfunction "+_1") (pintype "power_in"))
      (node (ref "Q2") (pin "2") (pinfunction "S_2") (pintype "bidirectional"))
      (node (ref "R28") (pin "2") (pinfunction "2_2") (pintype "passive"))
      (node (ref "U4") (pin "26") (pinfunction "PC3(ADC3)_26") (pintype "bidirectional"))
    )
    (net (code "82") (name "/VBATTTIMED") (class "Default")
      (node (ref "L1") (pin "P$1") (pinfunction "1_P$1") (pintype "passive"))
      (node (ref "Q2") (pin "3") (pinfunction "D_3") (pintype "bidirectional"))
    )
    (net (code "83") (name "/VCC_12") (class "Default")
      (node (ref "C1") (pin "1") (pinfunction "1_1") (pintype "passive"))
      (node (ref "C2") (pin "1") (pinfunction "1_1") (pintype "passive"))
      (node (ref "C3") (pin "1") (pinfunction "1_1") (pintype "passive"))
      (node (ref "C4") (pin "1") (pinfunction "1_1") (pintype "passive"))
      (node (ref "C5") (pin "1") (pinfunction "1_1") (pintype "passive"))
      (node (ref "C6") (pin "1") (pinfunction "1_1") (pintype "passive"))
      (node (ref "C7") (pin "1") (pinfunction "1_1") (pintype "passive"))
      (node (ref "C9") (pin "1") (pinfunction "1_1") (pintype "passive"))
      (node (ref "J8") (pin "2") (pinfunction "2_2") (pintype "passive"))
      (node (ref "U1") (pin "11") (pinfunction "VCC_11") (pintype "power_in"))
      (node (ref "U1") (pin "35") (pinfunction "VCC_35") (pintype "power_in"))
      (node (ref "U1") (pin "61") (pinfunction "VCC_61") (pintype "power_in"))
      (node (ref "U1") (pin "77") (pinfunction "VCC_77") (pintype "power_in"))
      (node (ref "U9") (pin "2") (pinfunction "OUT_2") (pintype "output"))
    )
    (net (code "84") (name "/VCC_33") (class "Default")
      (node (ref "C10") (pin "1") (pinfunction "1_1") (pintype "passive"))
      (node (ref "C11") (pin "1") (pinfunction "1_1") (pintype "passive"))
      (node (ref "C12") (pin "1") (pinfunction "1_1") (pintype "passive"))
      (node (ref "C13") (pin "1") (pinfunction "1_1") (pintype "passive"))
      (node (ref "C14") (pin "1") (pinfunction "1_1") (pintype "passive"))
      (node (ref "C15") (pin "1") (pinfunction "1_1") (pintype "passive"))
      (node (ref "C16") (pin "1") (pinfunction "1_1") (pintype "passive"))
      (node (ref "C17") (pin "1") (pinfunction "1_1") (pintype "passive"))
      (node (ref "C21") (pin "1") (pinfunction "1_1") (pintype "passive"))
      (node (ref "C22") (pin "1") (pinfunction "1_1") (pintype "passive"))
      (node (ref "C23") (pin "1") (pinfunction "1_1") (pintype "passive"))
      (node (ref "C24") (pin "1") (pinfunction "1_1") (pintype "passive"))
      (node (ref "D13") (pin "C") (pinfunction "C_C") (pintype "passive"))
      (node (ref "D14") (pin "C") (pinfunction "C_C") (pintype "passive"))
      (node (ref "J11") (pin "2") (pinfunction "2_2") (pintype "passive"))
      (node (ref "J12") (pin "5") (pinfunction "5_5") (pintype "passive"))
      (node (ref "J2") (pin "2") (pinfunction "2_2") (pintype "passive"))
      (node (ref "J4") (pin "3") (pinfunction "3_3") (pintype "passive"))
      (node (ref "R2") (pin "2") (pinfunction "2_2") (pintype "passive"))
      (node (ref "R5") (pin "2") (pinfunction "2_2") (pintype "passive"))
      (node (ref "R9") (pin "2") (pinfunction "2_2") (pintype "passive"))
      (node (ref "RN7") (pin "1") (pinfunction "1_1") (pintype "passive"))
      (node (ref "RN7") (pin "2") (pinfunction "1_2") (pintype "passive"))
      (node (ref "RN7") (pin "3") (pinfunction "1_3") (pintype "passive"))
      (node (ref "RN7") (pin "4") (pinfunction "1_4") (pintype "passive"))
      (node (ref "U1") (pin "14") (pinfunction "VCCIO_3_14") (pintype "power_in"))
      (node (ref "U1") (pin "22") (pinfunction "VCCIO_3_22") (pintype "power_in"))
      (node (ref "U1") (pin "31") (pinfunction "VCCIO_2_31") (pintype "power_in"))
      (node (ref "U1") (pin "38") (pinfunction "VCCIO_2_38") (pintype "power_in"))
      (node (ref "U1") (pin "50") (pinfunction "VCC_SPI_50") (pintype "power_in"))
      (node (ref "U1") (pin "58") (pinfunction "VCCIO_1_58") (pintype "power_in"))
      (node (ref "U1") (pin "6") (pinfunction "VCCIO_3_6") (pintype "power_in"))
      (node (ref "U1") (pin "67") (pinfunction "VCCIO_1_67") (pintype "power_in"))
      (node (ref "U1") (pin "75") (pinfunction "VPP_2V5_75") (pintype "power_in"))
      (node (ref "U1") (pin "88") (pinfunction "VCCIO_0_88") (pintype "power_in"))
      (node (ref "U1") (pin "92") (pinfunction "VCCIO_0_92") (pintype "power_in"))
      (node (ref "U2") (pin "4") (pinfunction "VCCIO_4") (pintype "power_in"))
      (node (ref "U3") (pin "3") (pinfunction "~{WP}(D2)_3") (pintype "bidirectional"))
      (node (ref "U3") (pin "7") (pinfunction "~{HOLD}(D3)_7") (pintype "bidirectional"))
      (node (ref "U3") (pin "8") (pinfunction "VCC_8") (pintype "bidirectional"))
      (node (ref "U4") (pin "13") (pinfunction "PB1(OC1A)_13") (pintype "bidirectional"))
      (node (ref "U4") (pin "18") (pinfunction "AVCC_18") (pintype "bidirectional"))
      (node (ref "U4") (pin "19") (pinfunction "ADC6_19") (pintype "bidirectional"))
      (node (ref "U4") (pin "20") (pinfunction "AREF_20") (pintype "bidirectional"))
      (node (ref "U4") (pin "4") (pinfunction "VCC_4") (pintype "bidirectional"))
      (node (ref "U4") (pin "6") (pinfunction "VCC_6") (pintype "bidirectional"))
      (node (ref "U9") (pin "3") (pinfunction "IN_3") (pintype "input"))
      (node (ref "Y2") (pin "1") (pinfunction "EN_1") (pintype "bidirectional"))
      (node (ref "Y2") (pin "4") (pinfunction "VCC_4") (pintype "bidirectional"))
    )
    (net (code "85") (name "/VPP_FAST") (class "Default")
      (node (ref "U1") (pin "76") (pinfunction "VPP_FAST_76") (pintype "power_in"))
    )
    (net (code "86") (name "/VUSB") (class "Default")
      (node (ref "C19") (pin "1") (pinfunction "1_1") (pintype "passive"))
      (node (ref "C20") (pin "1") (pinfunction "1_1") (pintype "passive"))
      (node (ref "IC1") (pin "8") (pinfunction "VCC_8") (pintype "power_in"))
      (node (ref "J4") (pin "1") (pinfunction "1_1") (pintype "passive"))
      (node (ref "R7") (pin "2") (pinfunction "2_2") (pintype "passive"))
      (node (ref "U2") (pin "20") (pinfunction "VCC_20") (pintype "power_in"))
      (node (ref "U7") (pin "3") (pinfunction "IN_3") (pintype "input"))
    )
    (net (code "87") (name "/VUSB_HALF") (class "Default")
      (node (ref "R7") (pin "1") (pinfunction "1_1") (pintype "passive"))
      (node (ref "R8") (pin "2") (pinfunction "2_2") (pintype "passive"))
      (node (ref "U4") (pin "25") (pinfunction "PC2(ADC2)_25") (pintype "bidirectional"))
    )
    (net (code "88") (name "/XT1") (class "Default")
      (node (ref "R4") (pin "1") (pinfunction "1_1") (pintype "passive"))
      (node (ref "U4") (pin "7") (pinfunction "PB6(XTAL1/TOSC1)_7") (pintype "bidirectional"))
      (node (ref "Y1") (pin "3") (pinfunction "3_3") (pintype "passive"))
    )
    (net (code "89") (name "/XT2") (class "Default")
      (node (ref "R4") (pin "2") (pinfunction "2_2") (pintype "passive"))
      (node (ref "U4") (pin "8") (pinfunction "PB7(XTAL2/TOSC2)_8") (pintype "bidirectional"))
      (node (ref "Y1") (pin "1") (pinfunction "1_1") (pintype "passive"))
    )
    (net (code "90") (name "GND") (class "Default")
      (node (ref "BT1") (pin "2") (pinfunction "-_2") (pintype "power_in"))
      (node (ref "C1") (pin "2") (pinfunction "2_2") (pintype "passive"))
      (node (ref "C10") (pin "2") (pinfunction "2_2") (pintype "passive"))
      (node (ref "C11") (pin "2") (pinfunction "2_2") (pintype "passive"))
      (node (ref "C12") (pin "2") (pinfunction "2_2") (pintype "passive"))
      (node (ref "C13") (pin "2") (pinfunction "2_2") (pintype "passive"))
      (node (ref "C14") (pin "2") (pinfunction "2_2") (pintype "passive"))
      (node (ref "C15") (pin "2") (pinfunction "2_2") (pintype "passive"))
      (node (ref "C16") (pin "2") (pinfunction "2_2") (pintype "passive"))
      (node (ref "C17") (pin "2") (pinfunction "2_2") (pintype "passive"))
      (node (ref "C18") (pin "2") (pinfunction "2_2") (pintype "passive"))
      (node (ref "C19") (pin "2") (pinfunction "2_2") (pintype "passive"))
      (node (ref "C2") (pin "2") (pinfunction "2_2") (pintype "passive"))
      (node (ref "C20") (pin "2") (pinfunction "2_2") (pintype "passive"))
      (node (ref "C21") (pin "2") (pinfunction "2_2") (pintype "passive"))
      (node (ref "C22") (pin "2") (pinfunction "2_2") (pintype "passive"))
      (node (ref "C23") (pin "2") (pinfunction "2_2") (pintype "passive"))
      (node (ref "C24") (pin "2") (pinfunction "2_2") (pintype "passive"))
      (node (ref "C25") (pin "2") (pinfunction "2_2") (pintype "passive"))
      (node (ref "C26") (pin "2") (pinfunction "2_2") (pintype "passive"))
      (node (ref "C3") (pin "2") (pinfunction "2_2") (pintype "passive"))
      (node (ref "C4") (pin "2") (pinfunction "2_2") (pintype "passive"))
      (node (ref "C5") (pin "2") (pinfunction "2_2") (pintype "passive"))
      (node (ref "C6") (pin "2") (pinfunction "2_2") (pintype "passive"))
      (node (ref "C7") (pin "2") (pinfunction "2_2") (pintype "passive"))
      (node (ref "C8") (pin "2") (pinfunction "2_2") (pintype "passive"))
      (node (ref "C9") (pin "2") (pinfunction "2_2") (pintype "passive"))
      (node (ref "D1") (pin "K") (pinfunction "C_K") (pintype "passive"))
      (node (ref "D10") (pin "K") (pinfunction "C_K") (pintype "passive"))
      (node (ref "D11") (pin "K") (pinfunction "C_K") (pintype "passive"))
      (node (ref "D12") (pin "K") (pinfunction "C_K") (pintype "passive"))
      (node (ref "D2") (pin "K") (pinfunction "C_K") (pintype "passive"))
      (node (ref "D3") (pin "K") (pinfunction "C_K") (pintype "passive"))
      (node (ref "D4") (pin "K") (pinfunction "C_K") (pintype "passive"))
      (node (ref "D5") (pin "K") (pinfunction "C_K") (pintype "passive"))
      (node (ref "D6") (pin "K") (pinfunction "C_K") (pintype "passive"))
      (node (ref "D7") (pin "K") (pinfunction "C_K") (pintype "passive"))
      (node (ref "D8") (pin "K") (pinfunction "C_K") (pintype "passive"))
      (node (ref "D9") (pin "K") (pinfunction "C_K") (pintype "passive"))
      (node (ref "IC1") (pin "4") (pinfunction "GND_4") (pintype "power_in"))
      (node (ref "IC1") (pin "5") (pinfunction "GND_5") (pintype "power_in"))
      (node (ref "J1") (pin "GND") (pinfunction "GND_GND") (pintype "power_in"))
      (node (ref "J11") (pin "7") (pinfunction "7_7") (pintype "passive"))
      (node (ref "J12") (pin "7") (pinfunction "7_7") (pintype "passive"))
      (node (ref "J2") (pin "6") (pinfunction "6_6") (pintype "passive"))
      (node (ref "J4") (pin "2") (pinfunction "2_2") (pintype "passive"))
      (node (ref "J5") (pin "1") (pinfunction "1_1") (pintype "passive"))
      (node (ref "J6") (pin "1") (pinfunction "1_1") (pintype "passive"))
      (node (ref "J8") (pin "1") (pinfunction "1_1") (pintype "passive"))
      (node (ref "Q1") (pin "2") (pinfunction "S_2") (pintype "bidirectional"))
      (node (ref "R1") (pin "2") (pinfunction "2_2") (pintype "passive"))
      (node (ref "R3") (pin "1") (pinfunction "1_1") (pintype "passive"))
      (node (ref "R6") (pin "1") (pinfunction "1_1") (pintype "passive"))
      (node (ref "R8") (pin "1") (pinfunction "1_1") (pintype "passive"))
      (node (ref "S1") (pin "1") (pinfunction "1_1") (pintype "passive"))
      (node (ref "S2") (pin "3") (pinfunction "2_3") (pintype "passive"))
      (node (ref "S3") (pin "3") (pinfunction "2_3") (pintype "passive"))
      (node (ref "S4") (pin "2") (pinfunction "P_2") (pintype "passive"))
      (node (ref "U$2") (pin "2") (pinfunction "GND_2") (pintype "bidirectional"))
      (node (ref "U1") (pin "17") (pinfunction "GND_17") (pintype "power_in"))
      (node (ref "U1") (pin "23") (pinfunction "GND_23") (pintype "power_in"))
      (node (ref "U1") (pin "32") (pinfunction "GND_32") (pintype "power_in"))
      (node (ref "U1") (pin "39") (pinfunction "GND_39") (pintype "power_in"))
      (node (ref "U1") (pin "47") (pinfunction "GND_47") (pintype "power_in"))
      (node (ref "U1") (pin "5") (pinfunction "GND_5") (pintype "power_in"))
      (node (ref "U1") (pin "55") (pinfunction "GND_55") (pintype "power_in"))
      (node (ref "U1") (pin "70") (pinfunction "GND_70") (pintype "power_in"))
      (node (ref "U1") (pin "84") (pinfunction "GND_84") (pintype "power_in"))
      (node (ref "U1") (pin "98") (pinfunction "GND_98") (pintype "power_in"))
      (node (ref "U2") (pin "18") (pinfunction "GND18_18") (pintype "power_in"))
      (node (ref "U2") (pin "21") (pinfunction "GND21_21") (pintype "power_in"))
      (node (ref "U2") (pin "7") (pinfunction "GND7_7") (pintype "power_in"))
      (node (ref "U3") (pin "4") (pinfunction "GND_4") (pintype "bidirectional"))
      (node (ref "U4") (pin "21") (pinfunction "AGND_21") (pintype "bidirectional"))
      (node (ref "U4") (pin "3") (pinfunction "GND_3") (pintype "bidirectional"))
      (node (ref "U4") (pin "5") (pinfunction "GND_5") (pintype "bidirectional"))
      (node (ref "U7") (pin "1") (pinfunction "ADJ_1") (pintype "input"))
      (node (ref "U9") (pin "1") (pinfunction "ADJ_1") (pintype "input"))
      (node (ref "Y1") (pin "2") (pinfunction "2_2") (pintype "passive"))
      (node (ref "Y2") (pin "2") (pinfunction "GND_2") (pintype "bidirectional"))
    )
    (net (code "91") (name "Net-(IC1-IO1-Pad2)") (class "Default")
      (node (ref "IC1") (pin "2") (pinfunction "IO1_2") (pintype "bidirectional"))
      (node (ref "J1") (pin "D+") (pinfunction "D+_D+") (pintype "bidirectional"))
    )
    (net (code "92") (name "Net-(IC1-IO2-Pad3)") (class "Default")
      (node (ref "IC1") (pin "3") (pinfunction "IO2_3") (pintype "bidirectional"))
      (node (ref "J1") (pin "D-") (pinfunction "D-_D-") (pintype "bidirectional"))
    )
    (net (code "93") (name "Net-(IC1-VCC-Pad1)") (class "Default")
      (node (ref "IC1") (pin "1") (pinfunction "VCC_1") (pintype "power_in"))
      (node (ref "J1") (pin "VBUS") (pinfunction "VBUS_VBUS") (pintype "power_in"))
    )
    (net (code "94") (name "Net-(J1-SHIELD-PadSHIELD1)") (class "Default")
      (node (ref "J1") (pin "SHIELD1") (pinfunction "SHIELD_SHIELD1") (pintype "bidirectional"))
      (node (ref "J1") (pin "SHIELD2") (pinfunction "SHIELD_SHIELD2") (pintype "bidirectional"))
      (node (ref "J1") (pin "SHIELD3") (pinfunction "SHIELD_SHIELD3") (pintype "bidirectional"))
      (node (ref "R1") (pin "1") (pinfunction "1_1") (pintype "passive"))
    )
    (net (code "95") (name "Net-(L1-2)") (class "Default")
      (node (ref "L1") (pin "P$2") (pinfunction "2_P$2") (pintype "passive"))
      (node (ref "U$2") (pin "1") (pinfunction "SW_1") (pintype "bidirectional"))
    )
    (net (code "96") (name "Net-(Q1-D)") (class "Default")
      (node (ref "C26") (pin "1") (pinfunction "1_1") (pintype "passive"))
      (node (ref "Q1") (pin "3") (pinfunction "D_3") (pintype "bidirectional"))
      (node (ref "Q2") (pin "1") (pinfunction "G_1") (pintype "bidirectional"))
      (node (ref "R28") (pin "1") (pinfunction "1_1") (pintype "passive"))
      (node (ref "S1") (pin "3") (pinfunction "2_3") (pintype "passive"))
      (node (ref "S4") (pin "3") (pinfunction "S_3") (pintype "passive"))
    )
    (net (code "97") (name "Net-(U$2-VOUT)") (class "Default")
      (node (ref "C25") (pin "1") (pinfunction "1_1") (pintype "passive"))
      (node (ref "C8") (pin "1") (pinfunction "1_1") (pintype "passive"))
      (node (ref "D13") (pin "A") (pinfunction "A_A") (pintype "passive"))
      (node (ref "J6") (pin "2") (pinfunction "2_2") (pintype "passive"))
      (node (ref "U$2") (pin "4") (pinfunction "VOUT_4") (pintype "bidirectional"))
    )
    (net (code "98") (name "Net-(U2-DTR)") (class "Default")
      (node (ref "C29") (pin "1") (pinfunction "1_1") (pintype "passive"))
      (node (ref "R6") (pin "2") (pinfunction "2_2") (pintype "passive"))
      (node (ref "U2") (pin "2") (pinfunction "DTR_2") (pintype "output"))
    )
    (net (code "99") (name "Net-(U2-VCCD)") (class "Default")
      (node (ref "C18") (pin "1") (pinfunction "1_1") (pintype "passive"))
      (node (ref "U2") (pin "17") (pinfunction "VCCD_17") (pintype "output"))
    )
    (net (code "100") (name "Net-(U7-OUT)") (class "Default")
      (node (ref "D14") (pin "A") (pinfunction "A_A") (pintype "passive"))
      (node (ref "J5") (pin "2") (pinfunction "2_2") (pintype "passive"))
      (node (ref "U7") (pin "2") (pinfunction "OUT_2") (pintype "output"))
    )
    (net (code "101") (name "unconnected-(J1-PadID)") (class "Default")
      (node (ref "J1") (pin "ID") (pinfunction "ID_ID") (pintype "bidirectional"))
    )
    (net (code "102") (name "unconnected-(J11-Pad3)") (class "Default")
      (node (ref "J11") (pin "3") (pinfunction "3_3") (pintype "passive"))
    )
    (net (code "103") (name "unconnected-(J11-Pad4)") (class "Default")
      (node (ref "J11") (pin "4") (pinfunction "4_4") (pintype "passive"))
    )
    (net (code "104") (name "unconnected-(J11-Pad5)") (class "Default")
      (node (ref "J11") (pin "5") (pinfunction "5_5") (pintype "passive"))
    )
    (net (code "105") (name "unconnected-(J11-Pad6)") (class "Default")
      (node (ref "J11") (pin "6") (pinfunction "6_6") (pintype "passive"))
    )
    (net (code "106") (name "unconnected-(J12-Pad1)") (class "Default")
      (node (ref "J12") (pin "1") (pinfunction "1_1") (pintype "passive"))
    )
    (net (code "107") (name "unconnected-(J12-Pad2)") (class "Default")
      (node (ref "J12") (pin "2") (pinfunction "2_2") (pintype "passive"))
    )
    (net (code "108") (name "unconnected-(J12-Pad6)") (class "Default")
      (node (ref "J12") (pin "6") (pinfunction "6_6") (pintype "passive"))
    )
    (net (code "109") (name "unconnected-(J12-Pad8)") (class "Default")
      (node (ref "J12") (pin "8") (pinfunction "8_8") (pintype "passive"))
    )
    (net (code "110") (name "unconnected-(S4-O-Pad1)") (class "Default")
      (node (ref "S4") (pin "1") (pinfunction "O_1") (pintype "passive"))
    )
    (net (code "111") (name "unconnected-(U1-IOB_26-Pad26)") (class "Default")
      (node (ref "U1") (pin "26") (pinfunction "IOB_26_26") (pintype "bidirectional"))
    )
    (net (code "112") (name "unconnected-(U1-IOB_27-Pad27)") (class "Default")
      (node (ref "U1") (pin "27") (pinfunction "IOB_27_27") (pintype "bidirectional"))
    )
    (net (code "113") (name "unconnected-(U1-IOB_28-Pad28)") (class "Default")
      (node (ref "U1") (pin "28") (pinfunction "IOB_28_28") (pintype "bidirectional"))
    )
    (net (code "114") (name "unconnected-(U1-IOB_29-Pad29)") (class "Default")
      (node (ref "U1") (pin "29") (pinfunction "IOB_29_29") (pintype "bidirectional"))
    )
    (net (code "115") (name "unconnected-(U1-IOB_30-Pad30)") (class "Default")
      (node (ref "U1") (pin "30") (pinfunction "IOB_30_30") (pintype "bidirectional"))
    )
    (net (code "116") (name "unconnected-(U1-IOB_34-Pad36)") (class "Default")
      (node (ref "U1") (pin "36") (pinfunction "IOB_34_36") (pintype "bidirectional"))
    )
    (net (code "117") (name "unconnected-(U1-IOB_35_GBIN5-Pad33)") (class "Default")
      (node (ref "U1") (pin "33") (pinfunction "IOB_35_GBIN5_33") (pintype "bidirectional"))
    )
    (net (code "118") (name "unconnected-(U1-IOL_1A-Pad1)") (class "Default")
      (node (ref "U1") (pin "1") (pinfunction "IOL_1A_1") (pintype "bidirectional"))
    )
    (net (code "119") (name "unconnected-(U1-IOL_1B-Pad2)") (class "Default")
      (node (ref "U1") (pin "2") (pinfunction "IOL_1B_2") (pintype "bidirectional"))
    )
    (net (code "120") (name "unconnected-(U1-IOL_2A-Pad3)") (class "Default")
      (node (ref "U1") (pin "3") (pinfunction "IOL_2A_3") (pintype "bidirectional"))
    )
    (net (code "121") (name "unconnected-(U1-IOL_2B-Pad4)") (class "Default")
      (node (ref "U1") (pin "4") (pinfunction "IOL_2B_4") (pintype "bidirectional"))
    )
    (net (code "122") (name "unconnected-(U1-IOL_3A-Pad7)") (class "Default")
      (node (ref "U1") (pin "7") (pinfunction "IOL_3A_7") (pintype "bidirectional"))
    )
    (net (code "123") (name "unconnected-(U1-IOL_7B-Pad16)") (class "Default")
      (node (ref "U1") (pin "16") (pinfunction "IOL_7B_16") (pintype "bidirectional"))
    )
    (net (code "124") (name "unconnected-(U1-IOL_12A-Pad24)") (class "Default")
      (node (ref "U1") (pin "24") (pinfunction "IOL_12A_24") (pintype "bidirectional"))
    )
    (net (code "125") (name "unconnected-(U1-IOL_12B-Pad25)") (class "Default")
      (node (ref "U1") (pin "25") (pinfunction "IOL_12B_25") (pintype "bidirectional"))
    )
    (net (code "126") (name "unconnected-(U1-IOR_58-Pad59)") (class "Default")
      (node (ref "U1") (pin "59") (pinfunction "IOR_58_59") (pintype "bidirectional"))
    )
    (net (code "127") (name "unconnected-(U1-IOR_59-Pad60)") (class "Default")
      (node (ref "U1") (pin "60") (pinfunction "IOR_59_60") (pintype "bidirectional"))
    )
    (net (code "128") (name "unconnected-(U1-IOR_65-Pad66)") (class "Default")
      (node (ref "U1") (pin "66") (pinfunction "IOR_65_66") (pintype "bidirectional"))
    )
    (net (code "129") (name "unconnected-(U1-IOR_67-Pad68)") (class "Default")
      (node (ref "U1") (pin "68") (pinfunction "IOR_67_68") (pintype "bidirectional"))
    )
    (net (code "130") (name "unconnected-(U1-IOR_68-Pad69)") (class "Default")
      (node (ref "U1") (pin "69") (pinfunction "IOR_68_69") (pintype "bidirectional"))
    )
    (net (code "131") (name "unconnected-(U1-IOR_69-Pad71)") (class "Default")
      (node (ref "U1") (pin "71") (pinfunction "IOR_69_71") (pintype "bidirectional"))
    )
    (net (code "132") (name "unconnected-(U1-IOR_70-Pad72)") (class "Default")
      (node (ref "U1") (pin "72") (pinfunction "IOR_70_72") (pintype "bidirectional"))
    )
    (net (code "133") (name "unconnected-(U1-IOT_82-Pad87)") (class "Default")
      (node (ref "U1") (pin "87") (pinfunction "IOT_82_87") (pintype "bidirectional"))
    )
    (net (code "134") (name "unconnected-(U1-IOT_86-Pad91)") (class "Default")
      (node (ref "U1") (pin "91") (pinfunction "IOT_86_91") (pintype "bidirectional"))
    )
    (net (code "135") (name "unconnected-(U1-IOT_87-Pad93)") (class "Default")
      (node (ref "U1") (pin "93") (pinfunction "IOT_87_93") (pintype "bidirectional"))
    )
    (net (code "136") (name "unconnected-(U1-IOT_88-Pad94)") (class "Default")
      (node (ref "U1") (pin "94") (pinfunction "IOT_88_94") (pintype "bidirectional"))
    )
    (net (code "137") (name "unconnected-(U1-IOT_89-Pad95)") (class "Default")
      (node (ref "U1") (pin "95") (pinfunction "IOT_89_95") (pintype "bidirectional"))
    )
    (net (code "138") (name "unconnected-(U1-IOT_90-Pad96)") (class "Default")
      (node (ref "U1") (pin "96") (pinfunction "IOT_90_96") (pintype "bidirectional"))
    )
    (net (code "139") (name "unconnected-(U1-IOT_91-Pad97)") (class "Default")
      (node (ref "U1") (pin "97") (pinfunction "IOT_91_97") (pintype "bidirectional"))
    )
    (net (code "140") (name "unconnected-(U1-IOT_93-Pad99)") (class "Default")
      (node (ref "U1") (pin "99") (pinfunction "IOT_93_99") (pintype "bidirectional"))
    )
    (net (code "141") (name "unconnected-(U1-IOT_95-Pad100)") (class "Default")
      (node (ref "U1") (pin "100") (pinfunction "IOT_95_100") (pintype "bidirectional"))
    )
    (net (code "142") (name "unconnected-(U2-CTS-Pad11)") (class "Default")
      (node (ref "U2") (pin "11") (pinfunction "CTS_11") (pintype "input"))
    )
    (net (code "143") (name "unconnected-(U2-DCD-Pad10)") (class "Default")
      (node (ref "U2") (pin "10") (pinfunction "DCD_10") (pintype "input"))
    )
    (net (code "144") (name "unconnected-(U2-DNU-Pad26)") (class "Default")
      (node (ref "U2") (pin "26") (pinfunction "DNU_26") (pintype "input"))
    )
    (net (code "145") (name "unconnected-(U2-DSR-Pad9)") (class "Default")
      (node (ref "U2") (pin "9") (pinfunction "DSR_9") (pintype "input"))
    )
    (net (code "146") (name "unconnected-(U2-GPIO5-Pad8)") (class "Default")
      (node (ref "U2") (pin "8") (pinfunction "GPIO5_8") (pintype "input"))
    )
    (net (code "147") (name "unconnected-(U2-NC0-Pad24)") (class "Default")
      (node (ref "U2") (pin "24") (pinfunction "NC0_24") (pintype "input"))
    )
    (net (code "148") (name "unconnected-(U2-OSCI-Pad27)") (class "Default")
      (node (ref "U2") (pin "27") (pinfunction "OSCI_27") (pintype "input"))
    )
    (net (code "149") (name "unconnected-(U2-OSCO-Pad28)") (class "Default")
      (node (ref "U2") (pin "28") (pinfunction "OSCO_28") (pintype "output"))
    )
    (net (code "150") (name "unconnected-(U2-PWREN-Pad14)") (class "Default")
      (node (ref "U2") (pin "14") (pinfunction "PWREN_14") (pintype "input"))
    )
    (net (code "151") (name "unconnected-(U2-RI-Pad6)") (class "Default")
      (node (ref "U2") (pin "6") (pinfunction "RI_6") (pintype "input"))
    )
    (net (code "152") (name "unconnected-(U2-RTS-Pad3)") (class "Default")
      (node (ref "U2") (pin "3") (pinfunction "RTS_3") (pintype "output"))
    )
    (net (code "153") (name "unconnected-(U2-RXLED-Pad22)") (class "Default")
      (node (ref "U2") (pin "22") (pinfunction "RXLED_22") (pintype "input"))
    )
    (net (code "154") (name "unconnected-(U2-SLEEP-Pad12)") (class "Default")
      (node (ref "U2") (pin "12") (pinfunction "SLEEP_12") (pintype "input"))
    )
    (net (code "155") (name "unconnected-(U2-TXDEN-Pad13)") (class "Default")
      (node (ref "U2") (pin "13") (pinfunction "TXDEN_13") (pintype "input"))
    )
    (net (code "156") (name "unconnected-(U2-TXLED-Pad23)") (class "Default")
      (node (ref "U2") (pin "23") (pinfunction "TXLED_23") (pintype "input"))
    )
    (net (code "157") (name "unconnected-(U4-ADC7-Pad22)") (class "Default")
      (node (ref "U4") (pin "22") (pinfunction "ADC7_22") (pintype "bidirectional"))
    )
    (net (code "158") (name "unconnected-(U4-PD2(INT0)-Pad32)") (class "Default")
      (node (ref "U4") (pin "32") (pinfunction "PD2(INT0)_32") (pintype "bidirectional"))
    )
    (net (code "159") (name "unconnected-(U4-PD3(INT1)-Pad1)") (class "Default")
      (node (ref "U4") (pin "1") (pinfunction "PD3(INT1)_1") (pintype "bidirectional"))
    )
  )
)
